# giraffe12.net
KiCad netlist of a schematic drawn in EAGLE
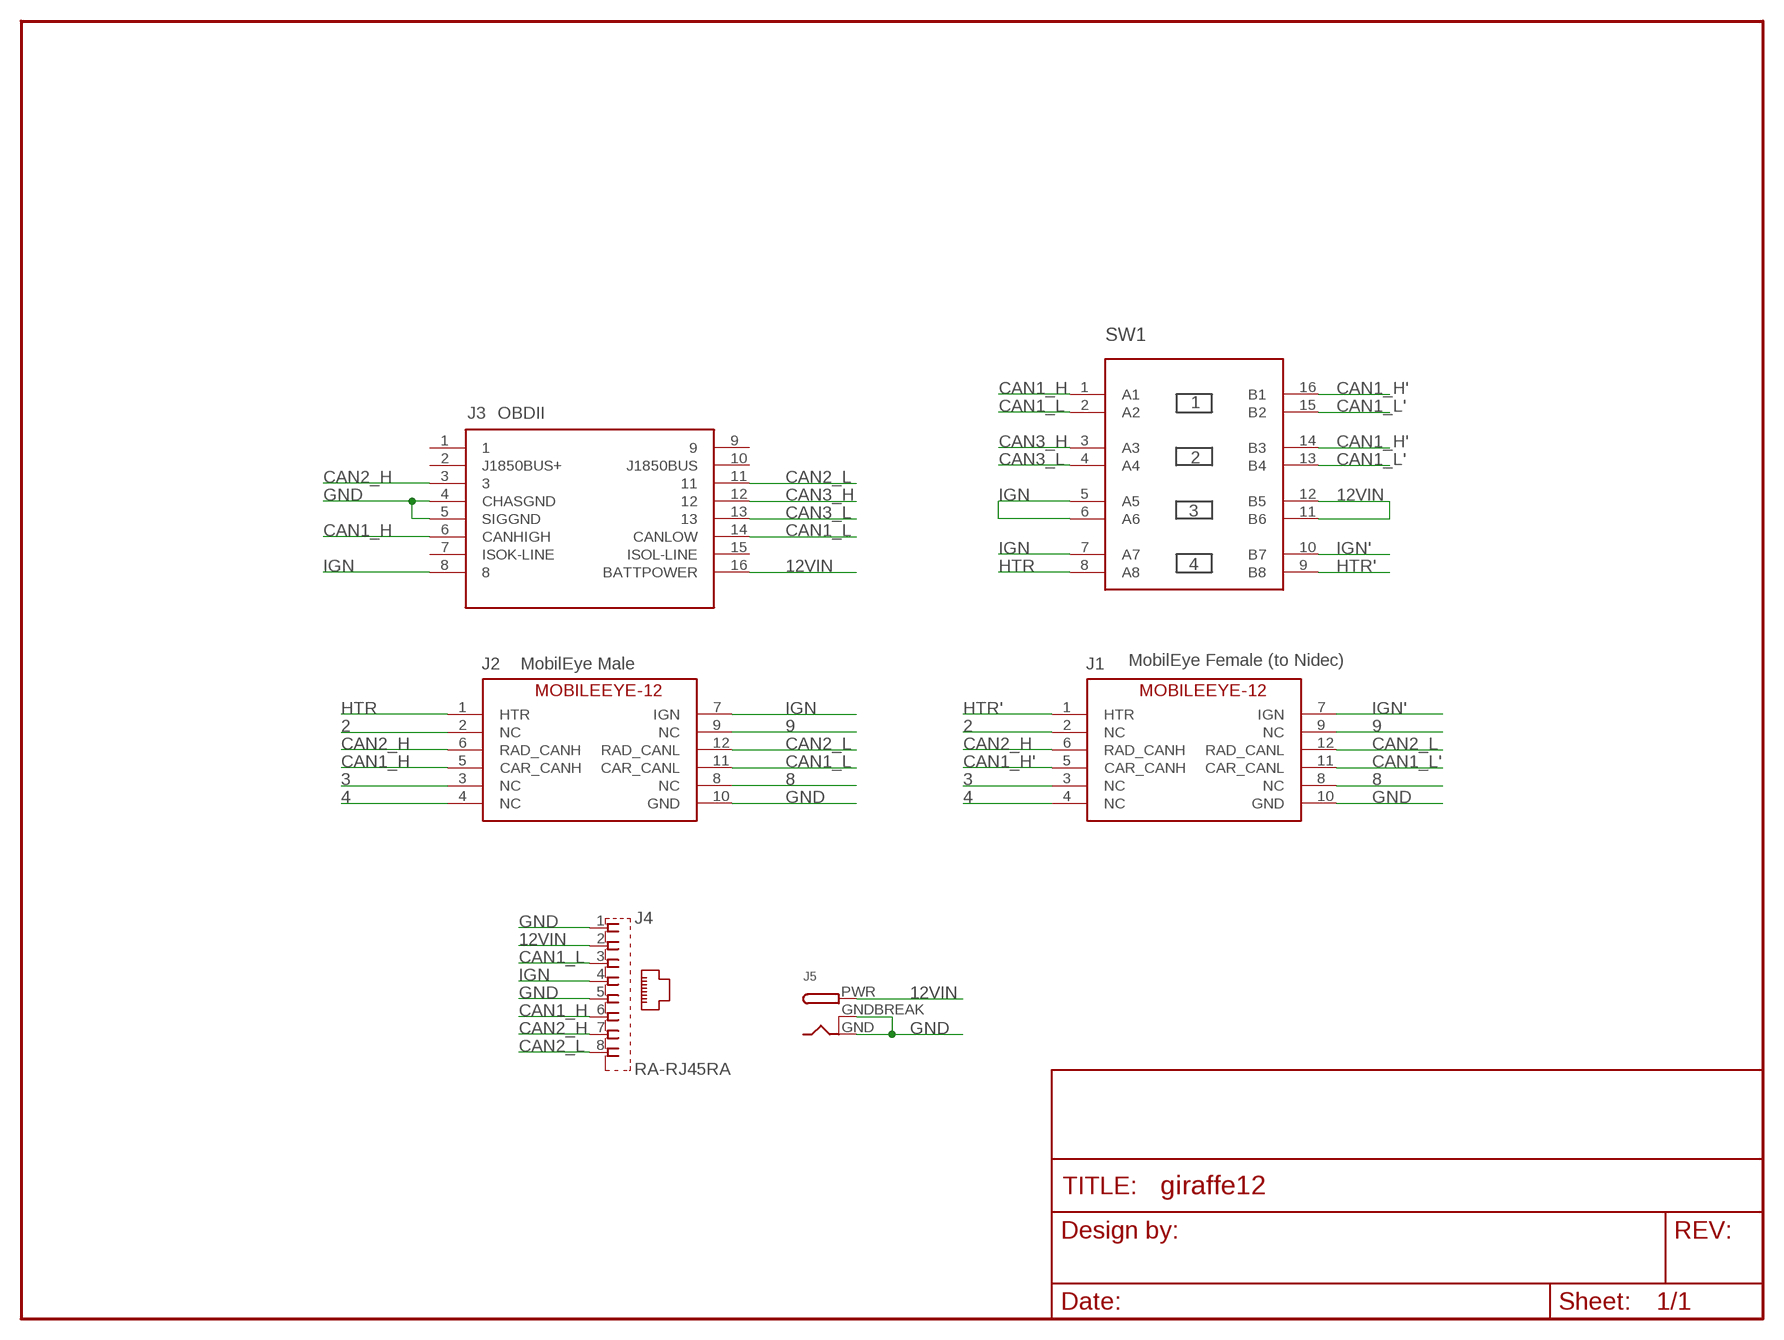
[diagram p0: schematic, sheet 1]

(export (version "E")
  (design (tool "Eeschema 10.0.6"))
  (components
    (comp (ref "FRAME1")
      (value "FRAME-LETTERNO_PACKAGE")
      (footprint "eagle-import:DUMMY")
      (fields (field (name "DESIGNER") "Nobody"))
      (libsource (lib "eagle-import") (part "FRAME-LETTERNO_PACKAGE"))
    )
    (comp (ref "J1")
      (value "MOBILEEYE-12FEMALE")
      (footprint "eagle-import:2X6-TE-FEMALE")
      (libsource (lib "eagle-import") (part "MOBILEEYE-12FEMALE"))
    )
    (comp (ref "J2")
      (value "MOBILEEYE-12MALE")
      (footprint "eagle-import:2X6-TE-RA")
      (libsource (lib "eagle-import") (part "MOBILEEYE-12MALE"))
    )
    (comp (ref "J3")
      (value "OBDII-FEMALE-CUT")
      (footprint "eagle-import:OBDII-FEMALE-MIDCUT")
      (libsource (lib "eagle-import") (part "OBDII-FEMALE-CUT"))
    )
    (comp (ref "J4")
      (value "RA-RJ45RA")
      (footprint "eagle-import:RA-RJ45")
      (libsource (lib "eagle-import") (part "RA-RJ45RA"))
    )
    (comp (ref "J5")
      (value "DCBARRELPTH")
      (footprint "eagle-import:DCJACK_2MM_PTH")
      (libsource (lib "eagle-import") (part "DCBARRELPTH"))
    )
    (comp (ref "SW1")
      (value "4XDPSTSMT")
      (footprint "eagle-import:4-DPST")
      (libsource (lib "eagle-import") (part "4XDPSTSMT"))
    )
  )
  (nets
    (net (code "1") (name "/2") (class "Default")
      (node (ref "J1") (pin "2") (pinfunction "NC_2") (pintype "bidirectional"))
      (node (ref "J2") (pin "2") (pinfunction "NC_2") (pintype "bidirectional"))
    )
    (net (code "2") (name "/3") (class "Default")
      (node (ref "J1") (pin "3") (pinfunction "NC_3") (pintype "bidirectional"))
      (node (ref "J2") (pin "3") (pinfunction "NC_3") (pintype "bidirectional"))
    )
    (net (code "3") (name "/4") (class "Default")
      (node (ref "J1") (pin "4") (pinfunction "NC_4") (pintype "bidirectional"))
      (node (ref "J2") (pin "4") (pinfunction "NC_4") (pintype "bidirectional"))
    )
    (net (code "4") (name "/8") (class "Default")
      (node (ref "J1") (pin "8") (pinfunction "NC_8") (pintype "bidirectional"))
      (node (ref "J2") (pin "8") (pinfunction "NC_8") (pintype "bidirectional"))
    )
    (net (code "5") (name "/9") (class "Default")
      (node (ref "J1") (pin "9") (pinfunction "NC_9") (pintype "bidirectional"))
      (node (ref "J2") (pin "9") (pinfunction "NC_9") (pintype "bidirectional"))
    )
    (net (code "6") (name "/12VIN") (class "Default")
      (node (ref "J3") (pin "16") (pinfunction "BATTPOWER_16") (pintype "bidirectional"))
      (node (ref "J4") (pin "2") (pinfunction "2_2") (pintype "passive"))
      (node (ref "J5") (pin "PWR") (pinfunction "PWR_PWR") (pintype "power_in"))
      (node (ref "SW1") (pin "11") (pinfunction "B6_11") (pintype "bidirectional"))
      (node (ref "SW1") (pin "12") (pinfunction "B5_12") (pintype "bidirectional"))
    )
    (net (code "7") (name "/CAN1_H") (class "Default")
      (node (ref "J2") (pin "5") (pinfunction "CAR_CANH_5") (pintype "bidirectional"))
      (node (ref "J3") (pin "6") (pinfunction "CANHIGH_6") (pintype "bidirectional"))
      (node (ref "J4") (pin "6") (pinfunction "6_6") (pintype "passive"))
      (node (ref "SW1") (pin "1") (pinfunction "A1_1") (pintype "bidirectional"))
    )
    (net (code "8") (name "/CAN1_H'") (class "Default")
      (node (ref "J1") (pin "5") (pinfunction "CAR_CANH_5") (pintype "bidirectional"))
      (node (ref "SW1") (pin "14") (pinfunction "B3_14") (pintype "bidirectional"))
      (node (ref "SW1") (pin "16") (pinfunction "B1_16") (pintype "bidirectional"))
    )
    (net (code "9") (name "/CAN1_L") (class "Default")
      (node (ref "J2") (pin "11") (pinfunction "CAR_CANL_11") (pintype "bidirectional"))
      (node (ref "J3") (pin "14") (pinfunction "CANLOW_14") (pintype "bidirectional"))
      (node (ref "J4") (pin "3") (pinfunction "3_3") (pintype "passive"))
      (node (ref "SW1") (pin "2") (pinfunction "A2_2") (pintype "bidirectional"))
    )
    (net (code "10") (name "/CAN1_L'") (class "Default")
      (node (ref "J1") (pin "11") (pinfunction "CAR_CANL_11") (pintype "bidirectional"))
      (node (ref "SW1") (pin "13") (pinfunction "B4_13") (pintype "bidirectional"))
      (node (ref "SW1") (pin "15") (pinfunction "B2_15") (pintype "bidirectional"))
    )
    (net (code "11") (name "/CAN2_H") (class "Default")
      (node (ref "J1") (pin "6") (pinfunction "RAD_CANH_6") (pintype "bidirectional"))
      (node (ref "J2") (pin "6") (pinfunction "RAD_CANH_6") (pintype "bidirectional"))
      (node (ref "J3") (pin "3") (pinfunction "3_3") (pintype "bidirectional"))
      (node (ref "J4") (pin "7") (pinfunction "7_7") (pintype "passive"))
    )
    (net (code "12") (name "/CAN2_L") (class "Default")
      (node (ref "J1") (pin "12") (pinfunction "RAD_CANL_12") (pintype "bidirectional"))
      (node (ref "J2") (pin "12") (pinfunction "RAD_CANL_12") (pintype "bidirectional"))
      (node (ref "J3") (pin "11") (pinfunction "11_11") (pintype "bidirectional"))
      (node (ref "J4") (pin "8") (pinfunction "8_8") (pintype "passive"))
    )
    (net (code "13") (name "/CAN3_H") (class "Default")
      (node (ref "J3") (pin "12") (pinfunction "12_12") (pintype "bidirectional"))
      (node (ref "SW1") (pin "3") (pinfunction "A3_3") (pintype "bidirectional"))
    )
    (net (code "14") (name "/CAN3_L") (class "Default")
      (node (ref "J3") (pin "13") (pinfunction "13_13") (pintype "bidirectional"))
      (node (ref "SW1") (pin "4") (pinfunction "A4_4") (pintype "bidirectional"))
    )
    (net (code "15") (name "/GND") (class "Default")
      (node (ref "J1") (pin "10") (pinfunction "GND_10") (pintype "bidirectional"))
      (node (ref "J2") (pin "10") (pinfunction "GND_10") (pintype "bidirectional"))
      (node (ref "J3") (pin "4") (pinfunction "CHASGND_4") (pintype "bidirectional"))
      (node (ref "J3") (pin "5") (pinfunction "SIGGND_5") (pintype "bidirectional"))
      (node (ref "J4") (pin "1") (pinfunction "1_1") (pintype "passive"))
      (node (ref "J4") (pin "5") (pinfunction "5_5") (pintype "passive"))
      (node (ref "J5") (pin "GND") (pinfunction "GND_GND") (pintype "power_in"))
      (node (ref "J5") (pin "GNDBREAK") (pinfunction "GNDBREAK_GNDBREAK") (pintype "power_in"))
    )
    (net (code "16") (name "/HTR") (class "Default")
      (node (ref "J2") (pin "1") (pinfunction "HTR_1") (pintype "bidirectional"))
      (node (ref "SW1") (pin "8") (pinfunction "A8_8") (pintype "bidirectional"))
    )
    (net (code "17") (name "/HTR'") (class "Default")
      (node (ref "J1") (pin "1") (pinfunction "HTR_1") (pintype "bidirectional"))
      (node (ref "SW1") (pin "9") (pinfunction "B8_9") (pintype "bidirectional"))
    )
    (net (code "18") (name "/IGN") (class "Default")
      (node (ref "J2") (pin "7") (pinfunction "IGN_7") (pintype "bidirectional"))
      (node (ref "J3") (pin "8") (pinfunction "8_8") (pintype "bidirectional"))
      (node (ref "J4") (pin "4") (pinfunction "4_4") (pintype "passive"))
      (node (ref "SW1") (pin "5") (pinfunction "A5_5") (pintype "bidirectional"))
      (node (ref "SW1") (pin "6") (pinfunction "A6_6") (pintype "bidirectional"))
      (node (ref "SW1") (pin "7") (pinfunction "A7_7") (pintype "bidirectional"))
    )
    (net (code "19") (name "/IGN'") (class "Default")
      (node (ref "J1") (pin "7") (pinfunction "IGN_7") (pintype "bidirectional"))
      (node (ref "SW1") (pin "10") (pinfunction "B7_10") (pintype "bidirectional"))
    )
    (net (code "20") (name "unconnected-(J3-ISOK-LINE-Pad7)") (class "Default")
      (node (ref "J3") (pin "7") (pinfunction "ISOK-LINE_7") (pintype "bidirectional"))
    )
    (net (code "21") (name "unconnected-(J3-ISOL-LINE-Pad15)") (class "Default")
      (node (ref "J3") (pin "15") (pinfunction "ISOL-LINE_15") (pintype "bidirectional"))
    )
    (net (code "22") (name "unconnected-(J3-J1850BUS+-Pad2)") (class "Default")
      (node (ref "J3") (pin "2") (pinfunction "J1850BUS+_2") (pintype "bidirectional"))
    )
    (net (code "23") (name "unconnected-(J3-J1850BUS-Pad10)") (class "Default")
      (node (ref "J3") (pin "10") (pinfunction "J1850BUS_10") (pintype "bidirectional"))
    )
    (net (code "24") (name "unconnected-(J3-Pad1)") (class "Default")
      (node (ref "J3") (pin "1") (pinfunction "1_1") (pintype "bidirectional"))
    )
    (net (code "25") (name "unconnected-(J3-Pad9)") (class "Default")
      (node (ref "J3") (pin "9") (pinfunction "9_9") (pintype "bidirectional"))
    )
  )
)
